# Logic_Level_Shifting.net
KiCad netlist of a schematic drawn in Altium Designer
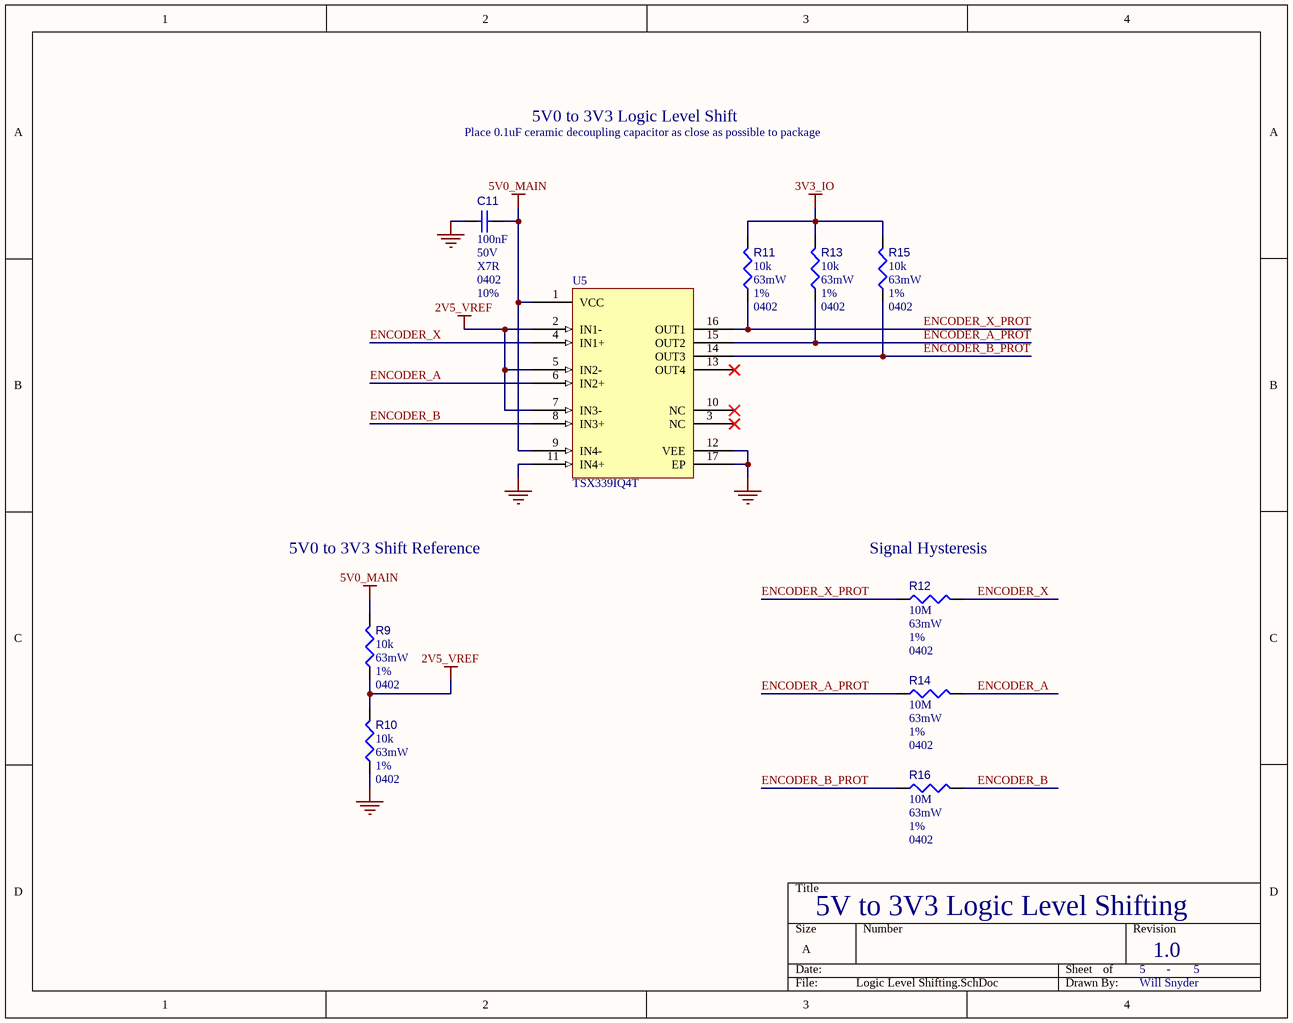
[diagram p0: Logic Level Shifting.SchDoc]

(export (version "E")
  (design (tool "Eeschema 10.0.6"))
  (components
    (comp (ref "C11")
      (value "100nF")
      (footprint "CAPC1005X55X30NL05T10")
      (fields
        (field (name "VOLTAGE RATING") "50V")
        (field (name "CAPACITOR TYPE") "X7R")
        (field (name "CASE/PACKAGE") "0402")
        (field (name "TOLERANCE") "10%")
        (field (name "Comment") "04025C104KAT4A")
      )
      (libsource (lib "Personal Workspace") (part "CAP-NP-2"))
    )
    (comp (ref "R9")
      (value "10k")
      (footprint "RESC1005X40X25NL05T05")
      (description "Fixed Resistor, Thin Film, 0.063W, 5100ohm, 50V, 1% +/-Tol, 50ppm/Cel, Surface Mount, 0402")
      (fields
        (field (name "POWER") "63mW")
        (field (name "TOLERANCE") "1%")
        (field (name "CASE/PACKAGE") "0402")
        (field (name "Comment") "MCS04020C5101FE000")
      )
      (libsource (lib "Personal Workspace") (part "RES-2"))
    )
    (comp (ref "R10")
      (value "10k")
      (footprint "RESC1005X40X25NL05T05")
      (description "Fixed Resistor, Thin Film, 0.063W, 5100ohm, 50V, 1% +/-Tol, 50ppm/Cel, Surface Mount, 0402")
      (fields
        (field (name "POWER") "63mW")
        (field (name "TOLERANCE") "1%")
        (field (name "CASE/PACKAGE") "0402")
        (field (name "Comment") "MCS04020C5101FE000")
      )
      (libsource (lib "Personal Workspace") (part "RES-2"))
    )
    (comp (ref "R11")
      (value "10k")
      (footprint "RESC1005X40X25NL05T05")
      (description "Fixed Resistor, Thin Film, 0.063W, 5100ohm, 50V, 1% +/-Tol, 50ppm/Cel, Surface Mount, 0402")
      (fields
        (field (name "POWER") "63mW")
        (field (name "TOLERANCE") "1%")
        (field (name "CASE/PACKAGE") "0402")
        (field (name "Comment") "MCS04020C5101FE000")
      )
      (libsource (lib "Personal Workspace") (part "RES-2"))
    )
    (comp (ref "R12")
      (value "10M")
      (footprint "RESC1005X40X25NL05T05")
      (description "Fixed Resistor, Thin Film, 0.063W, 5100ohm, 50V, 1% +/-Tol, 50ppm/Cel, Surface Mount, 0402")
      (fields
        (field (name "POWER") "63mW")
        (field (name "TOLERANCE") "1%")
        (field (name "CASE/PACKAGE") "0402")
        (field (name "Comment") "MCS04020C5101FE000")
      )
      (libsource (lib "Personal Workspace") (part "RES-2"))
    )
    (comp (ref "R13")
      (value "10k")
      (footprint "RESC1005X40X25NL05T05")
      (description "Fixed Resistor, Thin Film, 0.063W, 5100ohm, 50V, 1% +/-Tol, 50ppm/Cel, Surface Mount, 0402")
      (fields
        (field (name "POWER") "63mW")
        (field (name "TOLERANCE") "1%")
        (field (name "CASE/PACKAGE") "0402")
        (field (name "Comment") "MCS04020C5101FE000")
      )
      (libsource (lib "Personal Workspace") (part "RES-2"))
    )
    (comp (ref "R14")
      (value "10M")
      (footprint "RESC1005X40X25NL05T05")
      (description "Fixed Resistor, Thin Film, 0.063W, 5100ohm, 50V, 1% +/-Tol, 50ppm/Cel, Surface Mount, 0402")
      (fields
        (field (name "POWER") "63mW")
        (field (name "TOLERANCE") "1%")
        (field (name "CASE/PACKAGE") "0402")
        (field (name "Comment") "MCS04020C5101FE000")
      )
      (libsource (lib "Personal Workspace") (part "RES-2"))
    )
    (comp (ref "R15")
      (value "10k")
      (footprint "RESC1005X40X25NL05T05")
      (description "Fixed Resistor, Thin Film, 0.063W, 5100ohm, 50V, 1% +/-Tol, 50ppm/Cel, Surface Mount, 0402")
      (fields
        (field (name "POWER") "63mW")
        (field (name "TOLERANCE") "1%")
        (field (name "CASE/PACKAGE") "0402")
        (field (name "Comment") "MCS04020C5101FE000")
      )
      (libsource (lib "Personal Workspace") (part "RES-2"))
    )
    (comp (ref "R16")
      (value "10M")
      (footprint "RESC1005X40X25NL05T05")
      (description "Fixed Resistor, Thin Film, 0.063W, 5100ohm, 50V, 1% +/-Tol, 50ppm/Cel, Surface Mount, 0402")
      (fields
        (field (name "POWER") "63mW")
        (field (name "TOLERANCE") "1%")
        (field (name "CASE/PACKAGE") "0402")
        (field (name "Comment") "MCS04020C5101FE000")
      )
      (libsource (lib "Personal Workspace") (part "RES-2"))
    )
    (comp (ref "U5")
      (value "TSX339IQ4T")
      (footprint "QFN50P300X300X100-16N")
      (description "Comparator, 4 Func, 6000uV Offset-Max, 2500ns Response Time, CMOS")
      (libsource (lib "Personal Workspace") (part "TSX339IQ4T"))
    )
  )
  (nets
    (net (code "1") (name "/ENCODER_A") (class "Default")
      (node (ref "R14") (pin "1") (pinfunction "1_1") (pintype "passive"))
      (node (ref "U5") (pin "6") (pinfunction "IN2+_6") (pintype "input"))
    )
    (net (code "2") (name "/ENCODER_A_PROT") (class "Default")
      (node (ref "R13") (pin "2") (pinfunction "2_2") (pintype "passive"))
      (node (ref "R14") (pin "2") (pinfunction "2_2") (pintype "passive"))
      (node (ref "U5") (pin "15") (pinfunction "OUT2_15") (pintype "open_collector"))
    )
    (net (code "3") (name "/ENCODER_B") (class "Default")
      (node (ref "R16") (pin "1") (pinfunction "1_1") (pintype "passive"))
      (node (ref "U5") (pin "8") (pinfunction "IN3+_8") (pintype "input"))
    )
    (net (code "4") (name "/ENCODER_B_PROT") (class "Default")
      (node (ref "R15") (pin "2") (pinfunction "2_2") (pintype "passive"))
      (node (ref "R16") (pin "2") (pinfunction "2_2") (pintype "passive"))
      (node (ref "U5") (pin "14") (pinfunction "OUT3_14") (pintype "open_collector"))
    )
    (net (code "5") (name "/ENCODER_X") (class "Default")
      (node (ref "R12") (pin "1") (pinfunction "1_1") (pintype "passive"))
      (node (ref "U5") (pin "4") (pinfunction "IN1+_4") (pintype "input"))
    )
    (net (code "6") (name "/ENCODER_X_PROT") (class "Default")
      (node (ref "R11") (pin "2") (pinfunction "2_2") (pintype "passive"))
      (node (ref "R12") (pin "2") (pinfunction "2_2") (pintype "passive"))
      (node (ref "U5") (pin "16") (pinfunction "OUT1_16") (pintype "open_collector"))
    )
    (net (code "7") (name "2V5_VREF") (class "Default")
      (node (ref "R10") (pin "1") (pinfunction "1_1") (pintype "passive"))
      (node (ref "R9") (pin "2") (pinfunction "2_2") (pintype "passive"))
      (node (ref "U5") (pin "2") (pinfunction "IN1-_2") (pintype "input"))
      (node (ref "U5") (pin "5") (pinfunction "IN2-_5") (pintype "input"))
      (node (ref "U5") (pin "7") (pinfunction "IN3-_7") (pintype "input"))
    )
    (net (code "8") (name "3V3_IO") (class "Default")
      (node (ref "R11") (pin "1") (pinfunction "1_1") (pintype "passive"))
      (node (ref "R13") (pin "1") (pinfunction "1_1") (pintype "passive"))
      (node (ref "R15") (pin "1") (pinfunction "1_1") (pintype "passive"))
    )
    (net (code "9") (name "5V0_MAIN") (class "Default")
      (node (ref "C11") (pin "1") (pinfunction "1_1") (pintype "passive"))
      (node (ref "R9") (pin "1") (pinfunction "1_1") (pintype "passive"))
      (node (ref "U5") (pin "1") (pinfunction "VCC_1") (pintype "power_in"))
      (node (ref "U5") (pin "9") (pinfunction "IN4-_9") (pintype "input"))
    )
    (net (code "10") (name "GND") (class "Default")
      (node (ref "C11") (pin "2") (pinfunction "2_2") (pintype "passive"))
      (node (ref "R10") (pin "2") (pinfunction "2_2") (pintype "passive"))
      (node (ref "U5") (pin "11") (pinfunction "IN4+_11") (pintype "input"))
      (node (ref "U5") (pin "12") (pinfunction "VEE_12") (pintype "passive"))
      (node (ref "U5") (pin "17") (pinfunction "EP_17") (pintype "passive"))
    )
    (net (code "11") (name "unconnected-(U5-NC-Pad3)") (class "Default")
      (node (ref "U5") (pin "3") (pinfunction "NC_3") (pintype "passive+no_connect"))
    )
    (net (code "12") (name "unconnected-(U5-NC-Pad10)") (class "Default")
      (node (ref "U5") (pin "10") (pinfunction "NC_10") (pintype "passive+no_connect"))
    )
    (net (code "13") (name "unconnected-(U5-OUT4-Pad13)") (class "Default")
      (node (ref "U5") (pin "13") (pinfunction "OUT4_13") (pintype "open_collector+no_connect"))
    )
  )
)
